# Sheet1.net
KiCad netlist of a schematic drawn in Altium Designer
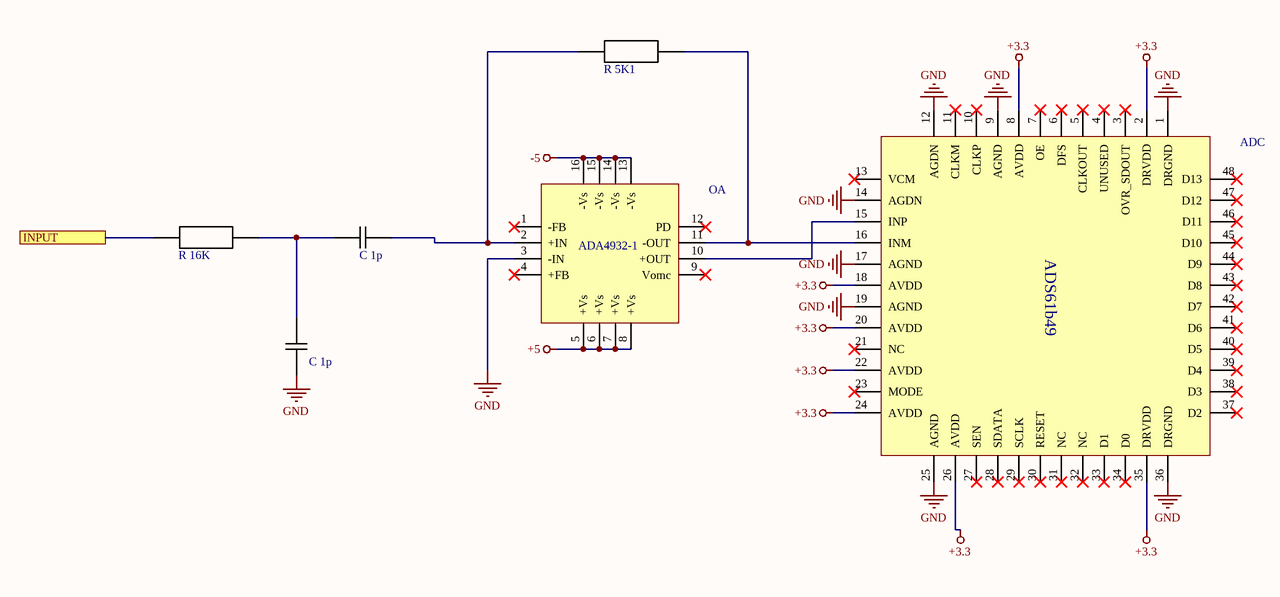
[diagram p0: Sheet1.SchDoc]

(export (version "E")
  (design (tool "Eeschema 10.0.6"))
  (components
    (comp (ref "1")
      (value "ADC")
      (footprint "PcbLib1:ADS61B49")
      (libsource (lib "altium-import") (part "root_3_ADC_"))
    )
    (comp (ref "2") (value "OA") (footprint "PcbLib1:ADA4932-1") (libsource (lib "Schlib1") (part "OA")))
    (comp (ref "3")
      (value "R 16K")
      (footprint "PcbLib1:R0805")
      (description "16K")
      (libsource (lib "altium-import") (part "root_0_R_"))
    )
    (comp (ref "4")
      (value "C 1p")
      (footprint "PcbLib1:С0805")
      (libsource (lib "altium-import") (part "root_0_C_"))
    )
    (comp (ref "8")
      (value "C 1p")
      (footprint "PcbLib1:С0805")
      (libsource (lib "altium-import") (part "root_1_C_"))
    )
    (comp (ref "9")
      (value "R 5K1")
      (footprint "PcbLib1:R0805")
      (libsource (lib "altium-import") (part "root_0_R_"))
    )
  )
  (nets
    (net (code "1") (name "+3.3") (class "Default")
      (node (ref "1") (pin "18") (pinfunction "AVDD_18") (pintype "passive"))
      (node (ref "1") (pin "2") (pinfunction "DRVDD_2") (pintype "passive"))
      (node (ref "1") (pin "20") (pinfunction "AVDD_20") (pintype "passive"))
      (node (ref "1") (pin "22") (pinfunction "AVDD_22") (pintype "passive"))
      (node (ref "1") (pin "24") (pinfunction "AVDD_24") (pintype "passive"))
      (node (ref "1") (pin "26") (pinfunction "AVDD_26") (pintype "passive"))
      (node (ref "1") (pin "35") (pinfunction "DRVDD_35") (pintype "passive"))
      (node (ref "1") (pin "8") (pinfunction "AVDD_8") (pintype "passive"))
    )
    (net (code "2") (name "+5") (class "Default")
      (node (ref "2") (pin "5") (pinfunction "+Vs_5") (pintype "passive"))
      (node (ref "2") (pin "6") (pinfunction "+Vs_6") (pintype "passive"))
      (node (ref "2") (pin "7") (pinfunction "+Vs_7") (pintype "passive"))
      (node (ref "2") (pin "8") (pinfunction "+Vs_8") (pintype "passive"))
    )
    (net (code "3") (name "-5") (class "Default")
      (node (ref "2") (pin "13") (pinfunction "-Vs_13") (pintype "passive"))
      (node (ref "2") (pin "14") (pinfunction "-Vs_14") (pintype "passive"))
      (node (ref "2") (pin "15") (pinfunction "-Vs_15") (pintype "passive"))
      (node (ref "2") (pin "16") (pinfunction "-Vs_16") (pintype "passive"))
    )
    (net (code "4") (name "/INPUT") (class "Default")
      (node (ref "3") (pin "1") (pinfunction "1_1") (pintype "passive"))
    )
    (net (code "5") (name "GND") (class "Default")
      (node (ref "1") (pin "1") (pinfunction "DRGND_1") (pintype "passive"))
      (node (ref "1") (pin "12") (pinfunction "AGDN_12") (pintype "passive"))
      (node (ref "1") (pin "14") (pinfunction "AGDN_14") (pintype "passive"))
      (node (ref "1") (pin "17") (pinfunction "AGND_17") (pintype "passive"))
      (node (ref "1") (pin "19") (pinfunction "AGND_19") (pintype "passive"))
      (node (ref "1") (pin "25") (pinfunction "AGND_25") (pintype "passive"))
      (node (ref "1") (pin "36") (pinfunction "DRGND_36") (pintype "passive"))
      (node (ref "1") (pin "9") (pinfunction "AGND_9") (pintype "passive"))
      (node (ref "2") (pin "3") (pinfunction "-IN_3") (pintype "passive"))
      (node (ref "8") (pin "1") (pinfunction "1_1") (pintype "passive"))
    )
    (net (code "6") (name "Net-(1-INM)") (class "Default")
      (node (ref "1") (pin "16") (pinfunction "INM_16") (pintype "passive"))
      (node (ref "2") (pin "11") (pinfunction "-OUT_11") (pintype "passive"))
      (node (ref "9") (pin "2") (pinfunction "2_2") (pintype "passive"))
    )
    (net (code "7") (name "Net-(1-INP)") (class "Default")
      (node (ref "1") (pin "15") (pinfunction "INP_15") (pintype "passive"))
      (node (ref "2") (pin "10") (pinfunction "+OUT_10") (pintype "passive"))
    )
    (net (code "8") (name "Net-(2-+IN)") (class "Default")
      (node (ref "2") (pin "2") (pinfunction "+IN_2") (pintype "passive"))
      (node (ref "4") (pin "2") (pinfunction "2_2") (pintype "passive"))
      (node (ref "9") (pin "1") (pinfunction "1_1") (pintype "passive"))
    )
    (net (code "9") (name "Net-(3-Pad2)") (class "Default")
      (node (ref "3") (pin "2") (pinfunction "2_2") (pintype "passive"))
      (node (ref "4") (pin "1") (pinfunction "1_1") (pintype "passive"))
      (node (ref "8") (pin "2") (pinfunction "2_2") (pintype "passive"))
    )
    (net (code "10") (name "unconnected-(1-CLKM-Pad11)") (class "Default")
      (node (ref "1") (pin "11") (pinfunction "CLKM_11") (pintype "passive+no_connect"))
    )
    (net (code "11") (name "unconnected-(1-CLKOUT-Pad5)") (class "Default")
      (node (ref "1") (pin "5") (pinfunction "CLKOUT_5") (pintype "passive+no_connect"))
    )
    (net (code "12") (name "unconnected-(1-CLKP-Pad10)") (class "Default")
      (node (ref "1") (pin "10") (pinfunction "CLKP_10") (pintype "passive+no_connect"))
    )
    (net (code "13") (name "unconnected-(1-D0-Pad34)") (class "Default")
      (node (ref "1") (pin "34") (pinfunction "D0_34") (pintype "passive+no_connect"))
    )
    (net (code "14") (name "unconnected-(1-D1-Pad33)") (class "Default")
      (node (ref "1") (pin "33") (pinfunction "D1_33") (pintype "passive+no_connect"))
    )
    (net (code "15") (name "unconnected-(1-D2-Pad37)") (class "Default")
      (node (ref "1") (pin "37") (pinfunction "D2_37") (pintype "passive+no_connect"))
    )
    (net (code "16") (name "unconnected-(1-D3-Pad38)") (class "Default")
      (node (ref "1") (pin "38") (pinfunction "D3_38") (pintype "passive+no_connect"))
    )
    (net (code "17") (name "unconnected-(1-D4-Pad39)") (class "Default")
      (node (ref "1") (pin "39") (pinfunction "D4_39") (pintype "passive+no_connect"))
    )
    (net (code "18") (name "unconnected-(1-D5-Pad40)") (class "Default")
      (node (ref "1") (pin "40") (pinfunction "D5_40") (pintype "passive+no_connect"))
    )
    (net (code "19") (name "unconnected-(1-D6-Pad41)") (class "Default")
      (node (ref "1") (pin "41") (pinfunction "D6_41") (pintype "passive+no_connect"))
    )
    (net (code "20") (name "unconnected-(1-D7-Pad42)") (class "Default")
      (node (ref "1") (pin "42") (pinfunction "D7_42") (pintype "passive+no_connect"))
    )
    (net (code "21") (name "unconnected-(1-D8-Pad43)") (class "Default")
      (node (ref "1") (pin "43") (pinfunction "D8_43") (pintype "passive+no_connect"))
    )
    (net (code "22") (name "unconnected-(1-D9-Pad44)") (class "Default")
      (node (ref "1") (pin "44") (pinfunction "D9_44") (pintype "passive+no_connect"))
    )
    (net (code "23") (name "unconnected-(1-D10-Pad45)") (class "Default")
      (node (ref "1") (pin "45") (pinfunction "D10_45") (pintype "passive+no_connect"))
    )
    (net (code "24") (name "unconnected-(1-D11-Pad46)") (class "Default")
      (node (ref "1") (pin "46") (pinfunction "D11_46") (pintype "passive+no_connect"))
    )
    (net (code "25") (name "unconnected-(1-D12-Pad47)") (class "Default")
      (node (ref "1") (pin "47") (pinfunction "D12_47") (pintype "passive+no_connect"))
    )
    (net (code "26") (name "unconnected-(1-D13-Pad48)") (class "Default")
      (node (ref "1") (pin "48") (pinfunction "D13_48") (pintype "passive+no_connect"))
    )
    (net (code "27") (name "unconnected-(1-DFS-Pad6)") (class "Default")
      (node (ref "1") (pin "6") (pinfunction "DFS_6") (pintype "passive+no_connect"))
    )
    (net (code "28") (name "unconnected-(1-MODE-Pad23)") (class "Default")
      (node (ref "1") (pin "23") (pinfunction "MODE_23") (pintype "passive+no_connect"))
    )
    (net (code "29") (name "unconnected-(1-NC-Pad21)") (class "Default")
      (node (ref "1") (pin "21") (pinfunction "NC_21") (pintype "passive+no_connect"))
    )
    (net (code "30") (name "unconnected-(1-NC-Pad31)") (class "Default")
      (node (ref "1") (pin "31") (pinfunction "NC_31") (pintype "passive+no_connect"))
    )
    (net (code "31") (name "unconnected-(1-NC-Pad32)") (class "Default")
      (node (ref "1") (pin "32") (pinfunction "NC_32") (pintype "passive+no_connect"))
    )
    (net (code "32") (name "unconnected-(1-OE-Pad7)") (class "Default")
      (node (ref "1") (pin "7") (pinfunction "OE_7") (pintype "passive+no_connect"))
    )
    (net (code "33") (name "unconnected-(1-OVR_SDOUT-Pad3)") (class "Default")
      (node (ref "1") (pin "3") (pinfunction "OVR_SDOUT_3") (pintype "passive+no_connect"))
    )
    (net (code "34") (name "unconnected-(1-RESET-Pad30)") (class "Default")
      (node (ref "1") (pin "30") (pinfunction "RESET_30") (pintype "passive+no_connect"))
    )
    (net (code "35") (name "unconnected-(1-SCLK-Pad29)") (class "Default")
      (node (ref "1") (pin "29") (pinfunction "SCLK_29") (pintype "passive+no_connect"))
    )
    (net (code "36") (name "unconnected-(1-SDATA-Pad28)") (class "Default")
      (node (ref "1") (pin "28") (pinfunction "SDATA_28") (pintype "passive+no_connect"))
    )
    (net (code "37") (name "unconnected-(1-SEN-Pad27)") (class "Default")
      (node (ref "1") (pin "27") (pinfunction "SEN_27") (pintype "passive+no_connect"))
    )
    (net (code "38") (name "unconnected-(1-UNUSED-Pad4)") (class "Default")
      (node (ref "1") (pin "4") (pinfunction "UNUSED_4") (pintype "passive+no_connect"))
    )
    (net (code "39") (name "unconnected-(1-VCM-Pad13)") (class "Default")
      (node (ref "1") (pin "13") (pinfunction "VCM_13") (pintype "passive+no_connect"))
    )
    (net (code "40") (name "unconnected-(2-+FB-Pad4)") (class "Default")
      (node (ref "2") (pin "4") (pinfunction "+FB_4") (pintype "passive+no_connect"))
    )
    (net (code "41") (name "unconnected-(2--FB-Pad1)") (class "Default")
      (node (ref "2") (pin "1") (pinfunction "-FB_1") (pintype "passive+no_connect"))
    )
    (net (code "42") (name "unconnected-(2-PD-Pad12)") (class "Default")
      (node (ref "2") (pin "12") (pinfunction "PD_12") (pintype "passive+no_connect"))
    )
    (net (code "43") (name "unconnected-(2-Vomc-Pad9)") (class "Default")
      (node (ref "2") (pin "9") (pinfunction "Vomc_9") (pintype "passive+no_connect"))
    )
  )
)
